# ReadySetNerds.net
KiCad netlist of a schematic drawn in EAGLE
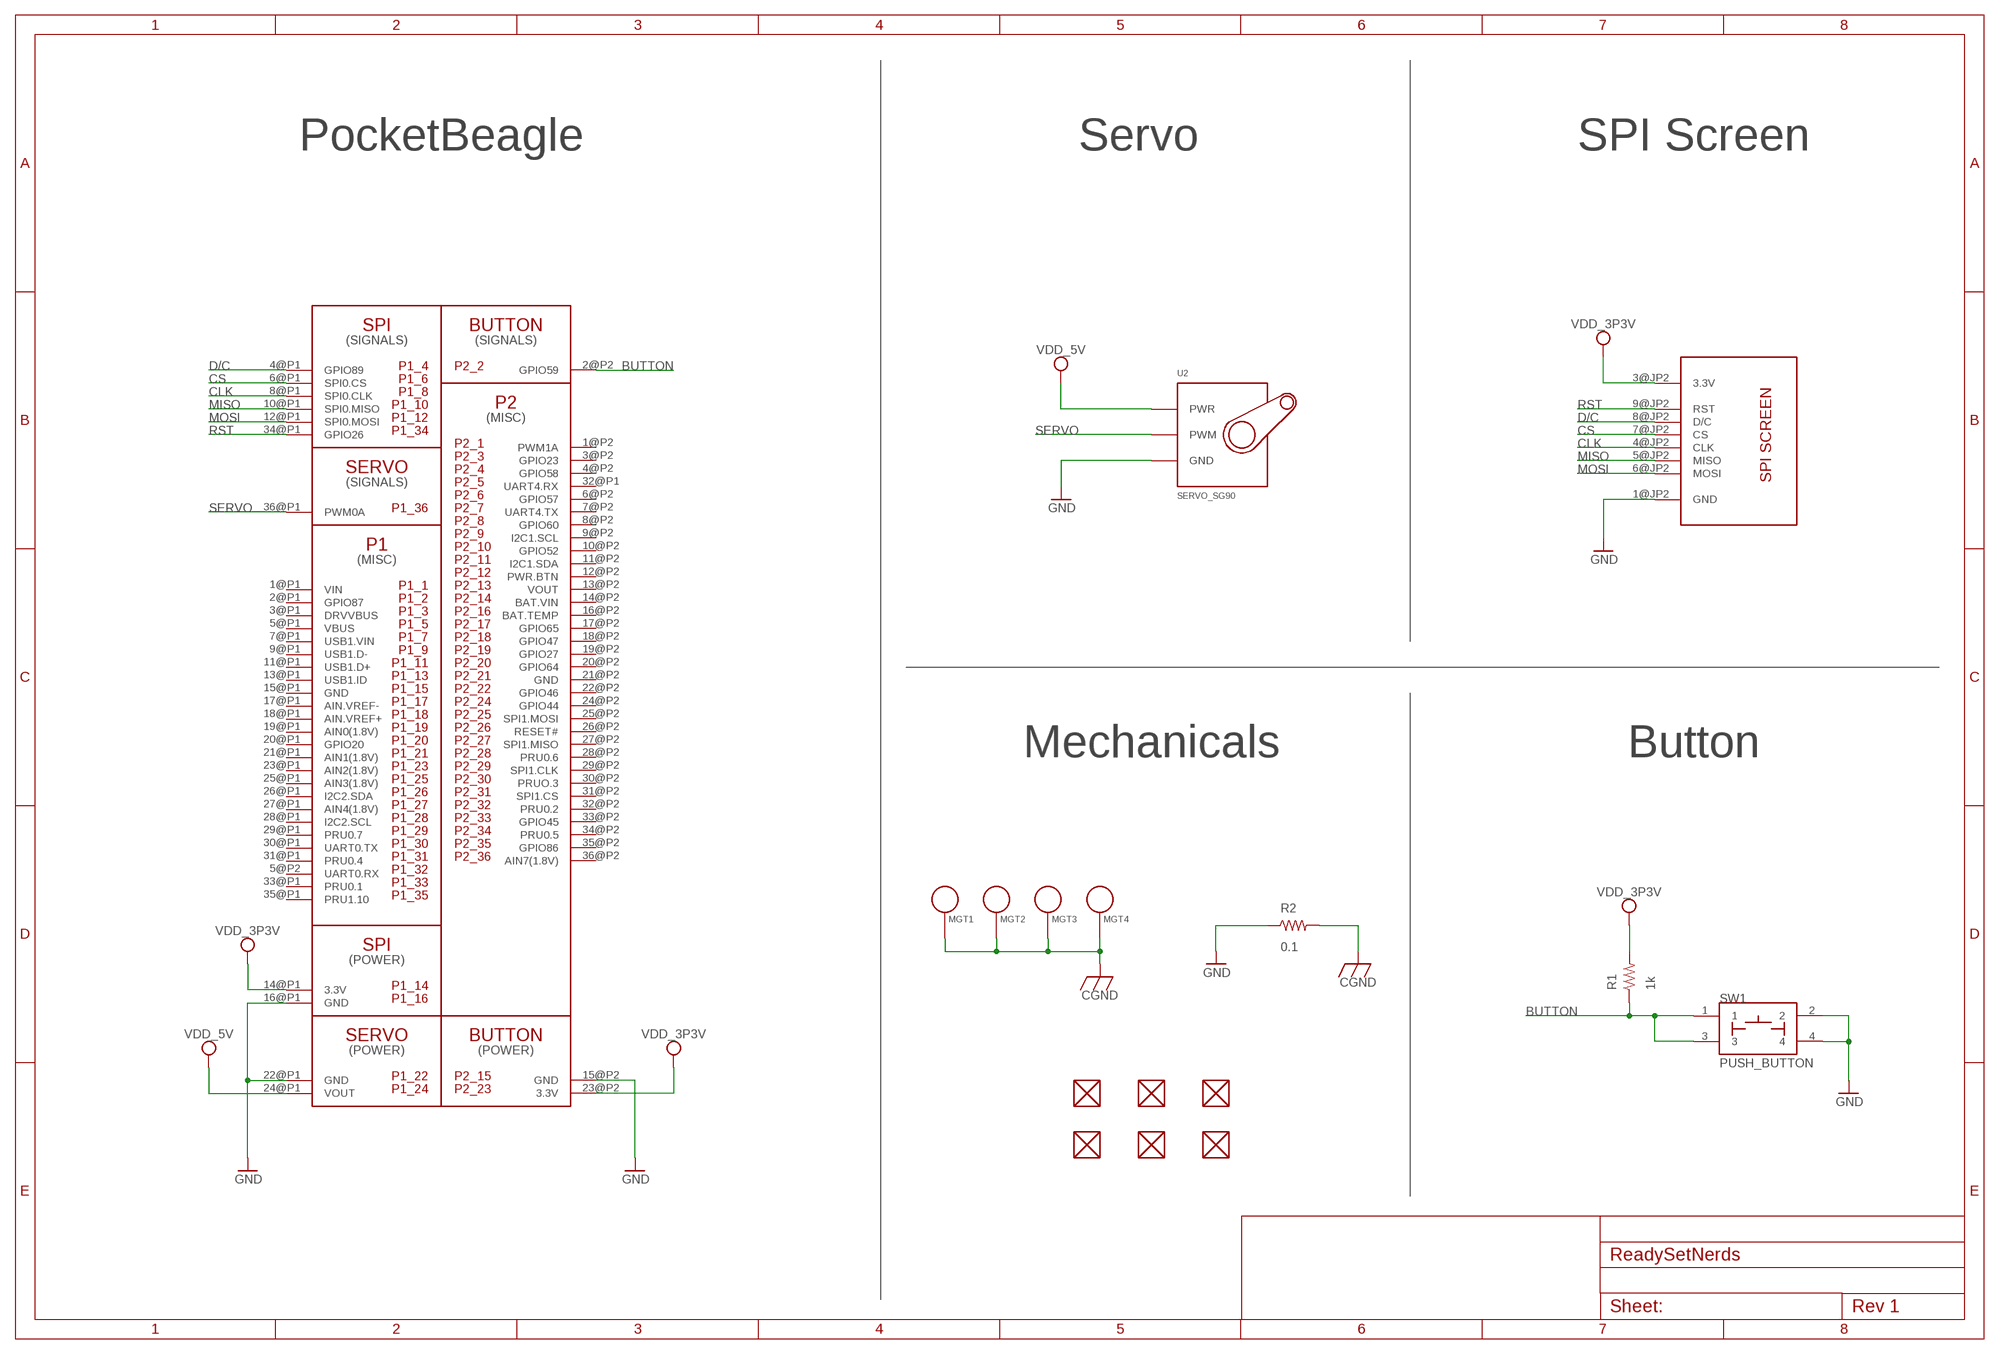
[diagram p0: schematic, sheet 1]

(export (version "E")
  (design (tool "Eeschema 10.0.6"))
  (components
    (comp (ref "FUD1")
      (value "FIDUCIAL")
      (footprint "eagle-import:FIDUCIAL_40MIL")
      (libsource (lib "eagle-import") (part "FIDUCIAL"))
    )
    (comp (ref "FUD2")
      (value "FIDUCIAL")
      (footprint "eagle-import:FIDUCIAL_40MIL")
      (libsource (lib "eagle-import") (part "FIDUCIAL"))
    )
    (comp (ref "FUD3")
      (value "FIDUCIAL")
      (footprint "eagle-import:FIDUCIAL_40MIL")
      (libsource (lib "eagle-import") (part "FIDUCIAL"))
    )
    (comp (ref "FUD4")
      (value "FIDUCIAL")
      (footprint "eagle-import:FIDUCIAL_40MIL")
      (libsource (lib "eagle-import") (part "FIDUCIAL"))
    )
    (comp (ref "FUD5")
      (value "FIDUCIAL")
      (footprint "eagle-import:FIDUCIAL_40MIL")
      (libsource (lib "eagle-import") (part "FIDUCIAL"))
    )
    (comp (ref "FUD6")
      (value "FIDUCIAL")
      (footprint "eagle-import:FIDUCIAL_40MIL")
      (libsource (lib "eagle-import") (part "FIDUCIAL"))
    )
    (comp (ref "MGT1")
      (value "MOUNTING_HOLE")
      (footprint "eagle-import:MOUNTING_HOLE")
      (libsource (lib "eagle-import") (part "MOUNTING_HOLE"))
    )
    (comp (ref "MGT2")
      (value "MOUNTING_HOLE")
      (footprint "eagle-import:MOUNTING_HOLE")
      (libsource (lib "eagle-import") (part "MOUNTING_HOLE"))
    )
    (comp (ref "MGT3")
      (value "MOUNTING_HOLE")
      (footprint "eagle-import:MOUNTING_HOLE")
      (libsource (lib "eagle-import") (part "MOUNTING_HOLE"))
    )
    (comp (ref "MGT4")
      (value "MOUNTING_HOLE")
      (footprint "eagle-import:MOUNTING_HOLE")
      (libsource (lib "eagle-import") (part "MOUNTING_HOLE"))
    )
    (comp (ref "R1")
      (value "1k")
      (footprint "eagle-import:R0603")
      (libsource (lib "eagle-import") (part "R_R0603"))
    )
    (comp (ref "R2")
      (value "0.1")
      (footprint "eagle-import:R0603")
      (libsource (lib "eagle-import") (part "R_R0603"))
    )
    (comp (ref "SW1")
      (value "PUSH_BUTTON")
      (footprint "eagle-import:BUTTON_12.5MM")
      (libsource (lib "eagle-import") (part "PUSH_BUTTON"))
    )
    (comp (ref "U$1")
      (value "POCKETBEAGLE")
      (footprint "eagle-import:POCKETBEAGLE")
      (libsource (lib "eagle-import") (part "POCKETBEAGLE"))
    )
    (comp (ref "U$2")
      (value "SPISCREEN")
      (footprint "eagle-import:SPISCREEN")
      (libsource (lib "eagle-import") (part "SPISCREEN"))
    )
    (comp (ref "U2")
      (value "SERVO_SG90")
      (footprint "eagle-import:SERVO-X1")
      (libsource (lib "eagle-import") (part "SERVO_SG90"))
    )
  )
  (nets
    (net (code "1") (name "/BUTTON") (class "Default")
      (node (ref "R1") (pin "1") (pinfunction "1_1") (pintype "passive"))
      (node (ref "SW1") (pin "1") (pinfunction "1_1") (pintype "bidirectional"))
      (node (ref "SW1") (pin "3") (pinfunction "3_3") (pintype "bidirectional"))
      (node (ref "U$1") (pin "2@P2") (pinfunction "GPIO59_2@P2") (pintype "bidirectional"))
    )
    (net (code "2") (name "/CLK") (class "Default")
      (node (ref "U$1") (pin "8@P1") (pinfunction "SPI0.CLK_8@P1") (pintype "bidirectional"))
      (node (ref "U$2") (pin "4@JP2") (pinfunction "CLK_4@JP2") (pintype "bidirectional"))
    )
    (net (code "3") (name "/CS") (class "Default")
      (node (ref "U$1") (pin "6@P1") (pinfunction "SPI0.CS_6@P1") (pintype "bidirectional"))
      (node (ref "U$2") (pin "7@JP2") (pinfunction "CS_7@JP2") (pintype "bidirectional"))
    )
    (net (code "4") (name "/D{slash}C") (class "Default")
      (node (ref "U$1") (pin "4@P1") (pinfunction "GPIO89_4@P1") (pintype "bidirectional"))
      (node (ref "U$2") (pin "8@JP2") (pinfunction "D/C_8@JP2") (pintype "bidirectional"))
    )
    (net (code "5") (name "/MISO") (class "Default")
      (node (ref "U$1") (pin "10@P1") (pinfunction "SPI0.MISO_10@P1") (pintype "bidirectional"))
      (node (ref "U$2") (pin "5@JP2") (pinfunction "MISO_5@JP2") (pintype "bidirectional"))
    )
    (net (code "6") (name "/MOSI") (class "Default")
      (node (ref "U$1") (pin "12@P1") (pinfunction "SPI0.MOSI_12@P1") (pintype "bidirectional"))
      (node (ref "U$2") (pin "6@JP2") (pinfunction "MOSI_6@JP2") (pintype "bidirectional"))
    )
    (net (code "7") (name "/RST") (class "Default")
      (node (ref "U$1") (pin "34@P1") (pinfunction "GPIO26_34@P1") (pintype "bidirectional"))
      (node (ref "U$2") (pin "9@JP2") (pinfunction "RST_9@JP2") (pintype "bidirectional"))
    )
    (net (code "8") (name "/SERVO") (class "Default")
      (node (ref "U$1") (pin "36@P1") (pinfunction "PWM0A_36@P1") (pintype "bidirectional"))
      (node (ref "U2") (pin "SIG") (pinfunction "PWM_SIG") (pintype "bidirectional"))
    )
    (net (code "9") (name "CGND") (class "Default")
      (node (ref "MGT1") (pin "P$1") (pinfunction "P$1_P$1") (pintype "bidirectional"))
      (node (ref "MGT2") (pin "P$1") (pinfunction "P$1_P$1") (pintype "bidirectional"))
      (node (ref "MGT3") (pin "P$1") (pinfunction "P$1_P$1") (pintype "bidirectional"))
      (node (ref "MGT4") (pin "P$1") (pinfunction "P$1_P$1") (pintype "bidirectional"))
      (node (ref "R2") (pin "2") (pinfunction "2_2") (pintype "passive"))
    )
    (net (code "10") (name "GND") (class "Default")
      (node (ref "R2") (pin "1") (pinfunction "1_1") (pintype "passive"))
      (node (ref "SW1") (pin "2") (pinfunction "2_2") (pintype "bidirectional"))
      (node (ref "SW1") (pin "4") (pinfunction "4_4") (pintype "bidirectional"))
      (node (ref "U$1") (pin "15@P2") (pinfunction "GND_15@P2") (pintype "bidirectional"))
      (node (ref "U$1") (pin "16@P1") (pinfunction "GND_16@P1") (pintype "bidirectional"))
      (node (ref "U$1") (pin "22@P1") (pinfunction "GND_22@P1") (pintype "bidirectional"))
      (node (ref "U$2") (pin "1@JP2") (pinfunction "GND_1@JP2") (pintype "bidirectional"))
      (node (ref "U2") (pin "GND") (pinfunction "GND_GND") (pintype "bidirectional"))
    )
    (net (code "11") (name "VDD_3P3V") (class "Default")
      (node (ref "R1") (pin "2") (pinfunction "2_2") (pintype "passive"))
      (node (ref "U$1") (pin "14@P1") (pinfunction "3.3V_14@P1") (pintype "bidirectional"))
      (node (ref "U$1") (pin "23@P2") (pinfunction "3.3V_23@P2") (pintype "bidirectional"))
      (node (ref "U$2") (pin "3@JP2") (pinfunction "3.3V_3@JP2") (pintype "bidirectional"))
    )
    (net (code "12") (name "VDD_5V") (class "Default")
      (node (ref "U$1") (pin "24@P1") (pinfunction "VOUT_24@P1") (pintype "bidirectional"))
      (node (ref "U2") (pin "PWR") (pinfunction "PWR_PWR") (pintype "bidirectional"))
    )
    (net (code "13") (name "unconnected-(FUD1-PadP$1)") (class "Default")
      (node (ref "FUD1") (pin "P$1") (pinfunction "P$1_P$1") (pintype "no_connect"))
    )
    (net (code "14") (name "unconnected-(FUD2-PadP$1)") (class "Default")
      (node (ref "FUD2") (pin "P$1") (pinfunction "P$1_P$1") (pintype "no_connect"))
    )
    (net (code "15") (name "unconnected-(FUD3-PadP$1)") (class "Default")
      (node (ref "FUD3") (pin "P$1") (pinfunction "P$1_P$1") (pintype "no_connect"))
    )
    (net (code "16") (name "unconnected-(FUD4-PadP$1)") (class "Default")
      (node (ref "FUD4") (pin "P$1") (pinfunction "P$1_P$1") (pintype "no_connect"))
    )
    (net (code "17") (name "unconnected-(FUD5-PadP$1)") (class "Default")
      (node (ref "FUD5") (pin "P$1") (pinfunction "P$1_P$1") (pintype "no_connect"))
    )
    (net (code "18") (name "unconnected-(FUD6-PadP$1)") (class "Default")
      (node (ref "FUD6") (pin "P$1") (pinfunction "P$1_P$1") (pintype "no_connect"))
    )
    (net (code "19") (name "unconnected-(U$1A-AIN.VREF+-Pad18@P1)") (class "Default")
      (node (ref "U$1") (pin "18@P1") (pinfunction "AIN.VREF+_18@P1") (pintype "bidirectional"))
    )
    (net (code "20") (name "unconnected-(U$1A-AIN.VREF--Pad17@P1)") (class "Default")
      (node (ref "U$1") (pin "17@P1") (pinfunction "AIN.VREF-_17@P1") (pintype "bidirectional"))
    )
    (net (code "21") (name "unconnected-(U$1A-AIN0(1.8V)-Pad19@P1)") (class "Default")
      (node (ref "U$1") (pin "19@P1") (pinfunction "AIN0(1.8V)_19@P1") (pintype "bidirectional"))
    )
    (net (code "22") (name "unconnected-(U$1A-AIN1(1.8V)-Pad21@P1)") (class "Default")
      (node (ref "U$1") (pin "21@P1") (pinfunction "AIN1(1.8V)_21@P1") (pintype "bidirectional"))
    )
    (net (code "23") (name "unconnected-(U$1A-AIN2(1.8V)-Pad23@P1)") (class "Default")
      (node (ref "U$1") (pin "23@P1") (pinfunction "AIN2(1.8V)_23@P1") (pintype "bidirectional"))
    )
    (net (code "24") (name "unconnected-(U$1A-AIN3(1.8V)-Pad25@P1)") (class "Default")
      (node (ref "U$1") (pin "25@P1") (pinfunction "AIN3(1.8V)_25@P1") (pintype "bidirectional"))
    )
    (net (code "25") (name "unconnected-(U$1A-AIN4(1.8V)-Pad27@P1)") (class "Default")
      (node (ref "U$1") (pin "27@P1") (pinfunction "AIN4(1.8V)_27@P1") (pintype "bidirectional"))
    )
    (net (code "26") (name "unconnected-(U$1A-AIN7(1.8V)-Pad36@P2)") (class "Default")
      (node (ref "U$1") (pin "36@P2") (pinfunction "AIN7(1.8V)_36@P2") (pintype "bidirectional"))
    )
    (net (code "27") (name "unconnected-(U$1A-BAT.TEMP-Pad16@P2)") (class "Default")
      (node (ref "U$1") (pin "16@P2") (pinfunction "BAT.TEMP_16@P2") (pintype "bidirectional"))
    )
    (net (code "28") (name "unconnected-(U$1A-BAT.VIN-Pad14@P2)") (class "Default")
      (node (ref "U$1") (pin "14@P2") (pinfunction "BAT.VIN_14@P2") (pintype "bidirectional"))
    )
    (net (code "29") (name "unconnected-(U$1A-DRVVBUS-Pad3@P1)") (class "Default")
      (node (ref "U$1") (pin "3@P1") (pinfunction "DRVVBUS_3@P1") (pintype "bidirectional"))
    )
    (net (code "30") (name "unconnected-(U$1A-GND-Pad15@P1)") (class "Default")
      (node (ref "U$1") (pin "15@P1") (pinfunction "GND_15@P1") (pintype "bidirectional"))
    )
    (net (code "31") (name "unconnected-(U$1A-GND-Pad21@P2)") (class "Default")
      (node (ref "U$1") (pin "21@P2") (pinfunction "GND_21@P2") (pintype "bidirectional"))
    )
    (net (code "32") (name "unconnected-(U$1A-GPIO20-Pad20@P1)") (class "Default")
      (node (ref "U$1") (pin "20@P1") (pinfunction "GPIO20_20@P1") (pintype "bidirectional"))
    )
    (net (code "33") (name "unconnected-(U$1A-GPIO23-Pad3@P2)") (class "Default")
      (node (ref "U$1") (pin "3@P2") (pinfunction "GPIO23_3@P2") (pintype "bidirectional"))
    )
    (net (code "34") (name "unconnected-(U$1A-GPIO27-Pad19@P2)") (class "Default")
      (node (ref "U$1") (pin "19@P2") (pinfunction "GPIO27_19@P2") (pintype "bidirectional"))
    )
    (net (code "35") (name "unconnected-(U$1A-GPIO44-Pad24@P2)") (class "Default")
      (node (ref "U$1") (pin "24@P2") (pinfunction "GPIO44_24@P2") (pintype "bidirectional"))
    )
    (net (code "36") (name "unconnected-(U$1A-GPIO45-Pad33@P2)") (class "Default")
      (node (ref "U$1") (pin "33@P2") (pinfunction "GPIO45_33@P2") (pintype "bidirectional"))
    )
    (net (code "37") (name "unconnected-(U$1A-GPIO46-Pad22@P2)") (class "Default")
      (node (ref "U$1") (pin "22@P2") (pinfunction "GPIO46_22@P2") (pintype "bidirectional"))
    )
    (net (code "38") (name "unconnected-(U$1A-GPIO47-Pad18@P2)") (class "Default")
      (node (ref "U$1") (pin "18@P2") (pinfunction "GPIO47_18@P2") (pintype "bidirectional"))
    )
    (net (code "39") (name "unconnected-(U$1A-GPIO52-Pad10@P2)") (class "Default")
      (node (ref "U$1") (pin "10@P2") (pinfunction "GPIO52_10@P2") (pintype "bidirectional"))
    )
    (net (code "40") (name "unconnected-(U$1A-GPIO57-Pad6@P2)") (class "Default")
      (node (ref "U$1") (pin "6@P2") (pinfunction "GPIO57_6@P2") (pintype "bidirectional"))
    )
    (net (code "41") (name "unconnected-(U$1A-GPIO58-Pad4@P2)") (class "Default")
      (node (ref "U$1") (pin "4@P2") (pinfunction "GPIO58_4@P2") (pintype "bidirectional"))
    )
    (net (code "42") (name "unconnected-(U$1A-GPIO60-Pad8@P2)") (class "Default")
      (node (ref "U$1") (pin "8@P2") (pinfunction "GPIO60_8@P2") (pintype "bidirectional"))
    )
    (net (code "43") (name "unconnected-(U$1A-GPIO64-Pad20@P2)") (class "Default")
      (node (ref "U$1") (pin "20@P2") (pinfunction "GPIO64_20@P2") (pintype "bidirectional"))
    )
    (net (code "44") (name "unconnected-(U$1A-GPIO65-Pad17@P2)") (class "Default")
      (node (ref "U$1") (pin "17@P2") (pinfunction "GPIO65_17@P2") (pintype "bidirectional"))
    )
    (net (code "45") (name "unconnected-(U$1A-GPIO86-Pad35@P2)") (class "Default")
      (node (ref "U$1") (pin "35@P2") (pinfunction "GPIO86_35@P2") (pintype "bidirectional"))
    )
    (net (code "46") (name "unconnected-(U$1A-GPIO87-Pad2@P1)") (class "Default")
      (node (ref "U$1") (pin "2@P1") (pinfunction "GPIO87_2@P1") (pintype "bidirectional"))
    )
    (net (code "47") (name "unconnected-(U$1A-I2C1.SCL-Pad9@P2)") (class "Default")
      (node (ref "U$1") (pin "9@P2") (pinfunction "I2C1.SCL_9@P2") (pintype "bidirectional"))
    )
    (net (code "48") (name "unconnected-(U$1A-I2C1.SDA-Pad11@P2)") (class "Default")
      (node (ref "U$1") (pin "11@P2") (pinfunction "I2C1.SDA_11@P2") (pintype "bidirectional"))
    )
    (net (code "49") (name "unconnected-(U$1A-I2C2.SCL-Pad28@P1)") (class "Default")
      (node (ref "U$1") (pin "28@P1") (pinfunction "I2C2.SCL_28@P1") (pintype "bidirectional"))
    )
    (net (code "50") (name "unconnected-(U$1A-I2C2.SDA-Pad26@P1)") (class "Default")
      (node (ref "U$1") (pin "26@P1") (pinfunction "I2C2.SDA_26@P1") (pintype "bidirectional"))
    )
    (net (code "51") (name "unconnected-(U$1A-PRU0.1-Pad33@P1)") (class "Default")
      (node (ref "U$1") (pin "33@P1") (pinfunction "PRU0.1_33@P1") (pintype "bidirectional"))
    )
    (net (code "52") (name "unconnected-(U$1A-PRU0.2-Pad32@P2)") (class "Default")
      (node (ref "U$1") (pin "32@P2") (pinfunction "PRU0.2_32@P2") (pintype "bidirectional"))
    )
    (net (code "53") (name "unconnected-(U$1A-PRU0.4-Pad31@P1)") (class "Default")
      (node (ref "U$1") (pin "31@P1") (pinfunction "PRU0.4_31@P1") (pintype "bidirectional"))
    )
    (net (code "54") (name "unconnected-(U$1A-PRU0.5-Pad34@P2)") (class "Default")
      (node (ref "U$1") (pin "34@P2") (pinfunction "PRU0.5_34@P2") (pintype "bidirectional"))
    )
    (net (code "55") (name "unconnected-(U$1A-PRU0.6-Pad28@P2)") (class "Default")
      (node (ref "U$1") (pin "28@P2") (pinfunction "PRU0.6_28@P2") (pintype "bidirectional"))
    )
    (net (code "56") (name "unconnected-(U$1A-PRU0.7-Pad29@P1)") (class "Default")
      (node (ref "U$1") (pin "29@P1") (pinfunction "PRU0.7_29@P1") (pintype "bidirectional"))
    )
    (net (code "57") (name "unconnected-(U$1A-PRU1.10-Pad35@P1)") (class "Default")
      (node (ref "U$1") (pin "35@P1") (pinfunction "PRU1.10_35@P1") (pintype "bidirectional"))
    )
    (net (code "58") (name "unconnected-(U$1A-PRUO.3-Pad30@P2)") (class "Default")
      (node (ref "U$1") (pin "30@P2") (pinfunction "PRUO.3_30@P2") (pintype "bidirectional"))
    )
    (net (code "59") (name "unconnected-(U$1A-PWM1A-Pad1@P2)") (class "Default")
      (node (ref "U$1") (pin "1@P2") (pinfunction "PWM1A_1@P2") (pintype "bidirectional"))
    )
    (net (code "60") (name "unconnected-(U$1A-PWR.BTN-Pad12@P2)") (class "Default")
      (node (ref "U$1") (pin "12@P2") (pinfunction "PWR.BTN_12@P2") (pintype "bidirectional"))
    )
    (net (code "61") (name "unconnected-(U$1A-RESET#-Pad26@P2)") (class "Default")
      (node (ref "U$1") (pin "26@P2") (pinfunction "RESET#_26@P2") (pintype "bidirectional"))
    )
    (net (code "62") (name "unconnected-(U$1A-SPI1.CLK-Pad29@P2)") (class "Default")
      (node (ref "U$1") (pin "29@P2") (pinfunction "SPI1.CLK_29@P2") (pintype "bidirectional"))
    )
    (net (code "63") (name "unconnected-(U$1A-SPI1.CS-Pad31@P2)") (class "Default")
      (node (ref "U$1") (pin "31@P2") (pinfunction "SPI1.CS_31@P2") (pintype "bidirectional"))
    )
    (net (code "64") (name "unconnected-(U$1A-SPI1.MISO-Pad27@P2)") (class "Default")
      (node (ref "U$1") (pin "27@P2") (pinfunction "SPI1.MISO_27@P2") (pintype "bidirectional"))
    )
    (net (code "65") (name "unconnected-(U$1A-SPI1.MOSI-Pad25@P2)") (class "Default")
      (node (ref "U$1") (pin "25@P2") (pinfunction "SPI1.MOSI_25@P2") (pintype "bidirectional"))
    )
    (net (code "66") (name "unconnected-(U$1A-UART0.RX-Pad5@P2)") (class "Default")
      (node (ref "U$1") (pin "5@P2") (pinfunction "UART0.RX_5@P2") (pintype "bidirectional"))
    )
    (net (code "67") (name "unconnected-(U$1A-UART0.TX-Pad30@P1)") (class "Default")
      (node (ref "U$1") (pin "30@P1") (pinfunction "UART0.TX_30@P1") (pintype "bidirectional"))
    )
    (net (code "68") (name "unconnected-(U$1A-UART4.RX-Pad32@P1)") (class "Default")
      (node (ref "U$1") (pin "32@P1") (pinfunction "UART4.RX_32@P1") (pintype "bidirectional"))
    )
    (net (code "69") (name "unconnected-(U$1A-UART4.TX-Pad7@P2)") (class "Default")
      (node (ref "U$1") (pin "7@P2") (pinfunction "UART4.TX_7@P2") (pintype "bidirectional"))
    )
    (net (code "70") (name "unconnected-(U$1A-USB1.D+-Pad11@P1)") (class "Default")
      (node (ref "U$1") (pin "11@P1") (pinfunction "USB1.D+_11@P1") (pintype "bidirectional"))
    )
    (net (code "71") (name "unconnected-(U$1A-USB1.D--Pad9@P1)") (class "Default")
      (node (ref "U$1") (pin "9@P1") (pinfunction "USB1.D-_9@P1") (pintype "bidirectional"))
    )
    (net (code "72") (name "unconnected-(U$1A-USB1.ID-Pad13@P1)") (class "Default")
      (node (ref "U$1") (pin "13@P1") (pinfunction "USB1.ID_13@P1") (pintype "bidirectional"))
    )
    (net (code "73") (name "unconnected-(U$1A-USB1.VIN-Pad7@P1)") (class "Default")
      (node (ref "U$1") (pin "7@P1") (pinfunction "USB1.VIN_7@P1") (pintype "bidirectional"))
    )
    (net (code "74") (name "unconnected-(U$1A-VBUS-Pad5@P1)") (class "Default")
      (node (ref "U$1") (pin "5@P1") (pinfunction "VBUS_5@P1") (pintype "bidirectional"))
    )
    (net (code "75") (name "unconnected-(U$1A-VIN-Pad1@P1)") (class "Default")
      (node (ref "U$1") (pin "1@P1") (pinfunction "VIN_1@P1") (pintype "bidirectional"))
    )
    (net (code "76") (name "unconnected-(U$1A-VOUT-Pad13@P2)") (class "Default")
      (node (ref "U$1") (pin "13@P2") (pinfunction "VOUT_13@P2") (pintype "bidirectional"))
    )
  )
)
